# Encoder.net
KiCad netlist of a schematic drawn in Altium Designer
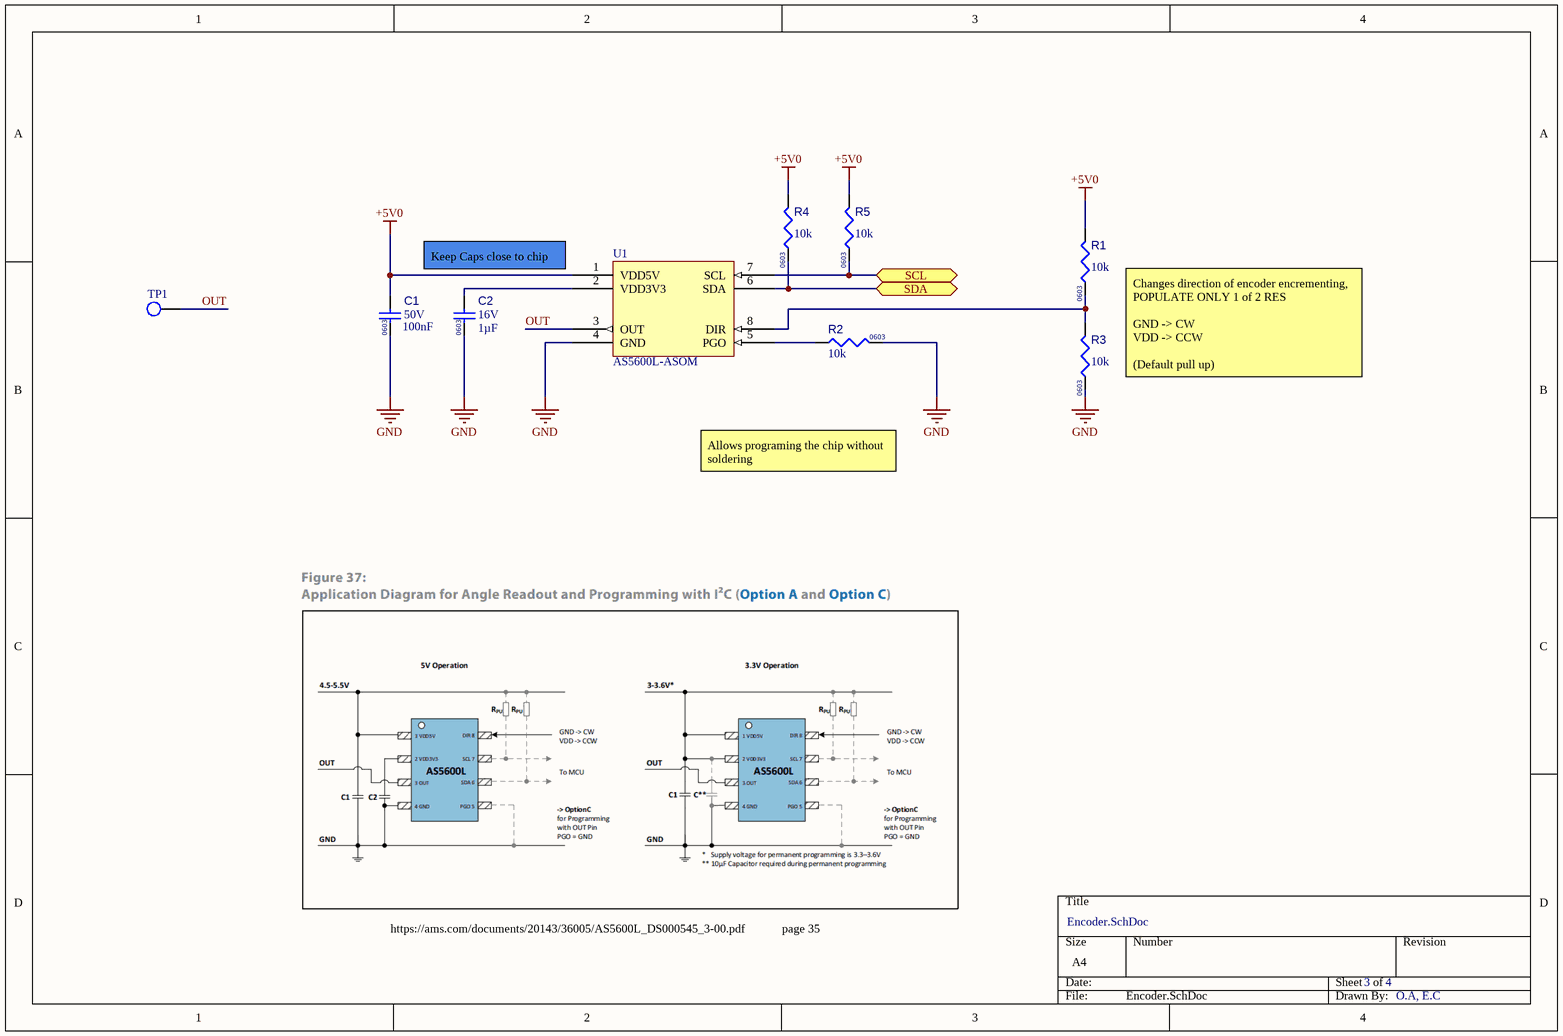
[diagram p0: Encoder.SchDoc]

(export (version "E")
  (design (tool "Eeschema 10.0.6"))
  (components
    (comp (ref "C1")
      (value "100nF")
      (footprint "CAPC1608X90X40NL10T20")
      (description "Chip Capacitor, 100 nF, +/- 10%, 50 V, 0603 (1608 Metric)")
      (fields
        (field (name "TOLERANCE") "10%")
        (field (name "VOLTAGE RATING") "50V")
        (field (name "CASE/PACKAGE") "0603")
        (field (name "Comment") "Capacitor 100 nF +/-10% 50 V 0603")
      )
      (libsource (lib "hawaiirobotics") (part "CAP-NP-2"))
    )
    (comp (ref "C2")
      (value "1µF")
      (footprint "CAPC1608X90X35NL15T15")
      (description "Chip Capacitor, 1 uF, +/- 10%, 16 V, 0603 (1608 Metric)")
      (fields
        (field (name "CASE/PACKAGE") "0603")
        (field (name "VOLTAGE RATING") "16V")
        (field (name "TOLERANCE") "10%")
        (field (name "Comment") "Capacitor 1uF +/- 10% 16V 0603")
      )
      (libsource (lib "hawaiirobotics") (part "CAP-NP-2"))
    )
    (comp (ref "R1")
      (value "10k")
      (footprint "RESC1608X55X25NL10T15")
      (description "Chip Resistor, 10 KOhm, +/- 1%, 01 W, -55 to 155 degC, 0603 (1608 Metric)")
      (fields
        (field (name "CASE/PACKAGE") "0603")
        (field (name "POWER") "100mW")
        (field (name "TOLERANCE") "1%")
      )
      (libsource (lib "hawaiirobotics") (part "RES-2"))
    )
    (comp (ref "R2")
      (value "10k")
      (footprint "RESC1608X55X25NL10T15")
      (description "Chip Resistor, 10 KOhm, +/- 1%, 01 W, -55 to 155 degC, 0603 (1608 Metric)")
      (fields
        (field (name "CASE/PACKAGE") "0603")
        (field (name "POWER") "100mW")
        (field (name "TOLERANCE") "1%")
      )
      (libsource (lib "hawaiirobotics") (part "RES-2"))
    )
    (comp (ref "R3")
      (value "10k")
      (footprint "RESC1608X55X25NL10T15")
      (description "Chip Resistor, 10 KOhm, +/- 1%, 01 W, -55 to 155 degC, 0603 (1608 Metric)")
      (fields
        (field (name "CASE/PACKAGE") "0603")
        (field (name "POWER") "100mW")
        (field (name "TOLERANCE") "1%")
      )
      (libsource (lib "hawaiirobotics") (part "RES-2"))
    )
    (comp (ref "R4")
      (value "10k")
      (footprint "RESC1608X55X25NL10T15")
      (description "Chip Resistor, 10 KOhm, +/- 1%, 01 W, -55 to 155 degC, 0603 (1608 Metric)")
      (fields
        (field (name "CASE/PACKAGE") "0603")
        (field (name "POWER") "100mW")
        (field (name "TOLERANCE") "1%")
      )
      (libsource (lib "hawaiirobotics") (part "RES-2"))
    )
    (comp (ref "R5")
      (value "10k")
      (footprint "RESC1608X55X25NL10T15")
      (description "Chip Resistor, 10 KOhm, +/- 1%, 01 W, -55 to 155 degC, 0603 (1608 Metric)")
      (fields
        (field (name "CASE/PACKAGE") "0603")
        (field (name "POWER") "100mW")
        (field (name "TOLERANCE") "1%")
      )
      (libsource (lib "hawaiirobotics") (part "RES-2"))
    )
    (comp (ref "TP1")
      (value "RCUCTE")
      (footprint "FP-S2761-46R-MFG")
      (description "Test point")
      (libsource (lib "hawaiirobotics") (part "RCUCTE-Symbol-1"))
    )
    (comp (ref "U1")
      (value "AS5600L-ASOM")
      (footprint "AS5600L-ASOM-Footprint-1")
      (description "AS5600L Series 12-Bit Programmable On-Axis Magnetic Rotary Position Sensor")
      (libsource (lib "hawaiirobotics") (part "AS5600L-ASOM-Symbol-1"))
    )
  )
  (nets
    (net (code "1") (name "+5V0") (class "Default")
      (node (ref "C1") (pin "2") (pinfunction "2_2") (pintype "passive"))
      (node (ref "R1") (pin "2") (pinfunction "2_2") (pintype "passive"))
      (node (ref "R4") (pin "2") (pinfunction "2_2") (pintype "passive"))
      (node (ref "R5") (pin "2") (pinfunction "2_2") (pintype "passive"))
      (node (ref "U1") (pin "1") (pinfunction "VDD5V_1") (pintype "power_in"))
    )
    (net (code "2") (name "/OUT") (class "Default")
      (node (ref "TP1") (pin "1") (pinfunction "1_1") (pintype "passive"))
      (node (ref "U1") (pin "3") (pinfunction "OUT_3") (pintype "output"))
    )
    (net (code "3") (name "/SCL") (class "Default")
      (node (ref "R5") (pin "1") (pinfunction "1_1") (pintype "passive"))
      (node (ref "U1") (pin "7") (pinfunction "SCL_7") (pintype "input"))
    )
    (net (code "4") (name "/SDA") (class "Default")
      (node (ref "R4") (pin "1") (pinfunction "1_1") (pintype "passive"))
      (node (ref "U1") (pin "6") (pinfunction "SDA_6") (pintype "open_collector"))
    )
    (net (code "5") (name "GND") (class "Default")
      (node (ref "C1") (pin "1") (pinfunction "1_1") (pintype "passive"))
      (node (ref "C2") (pin "1") (pinfunction "1_1") (pintype "passive"))
      (node (ref "R2") (pin "2") (pinfunction "2_2") (pintype "passive"))
      (node (ref "R3") (pin "1") (pinfunction "1_1") (pintype "passive"))
      (node (ref "U1") (pin "4") (pinfunction "GND_4") (pintype "power_in"))
    )
    (net (code "6") (name "Net-(U1-DIR)") (class "Default")
      (node (ref "R1") (pin "1") (pinfunction "1_1") (pintype "passive"))
      (node (ref "R3") (pin "2") (pinfunction "2_2") (pintype "passive"))
      (node (ref "U1") (pin "8") (pinfunction "DIR_8") (pintype "input"))
    )
    (net (code "7") (name "Net-(U1-PGO)") (class "Default")
      (node (ref "R2") (pin "1") (pinfunction "1_1") (pintype "passive"))
      (node (ref "U1") (pin "5") (pinfunction "PGO_5") (pintype "input"))
    )
    (net (code "8") (name "Net-(U1-VDD3V3)") (class "Default")
      (node (ref "C2") (pin "2") (pinfunction "2_2") (pintype "passive"))
      (node (ref "U1") (pin "2") (pinfunction "VDD3V3_2") (pintype "power_in"))
    )
  )
)
